# opt2bnc_trigger.net
KiCad netlist of a schematic drawn in EAGLE
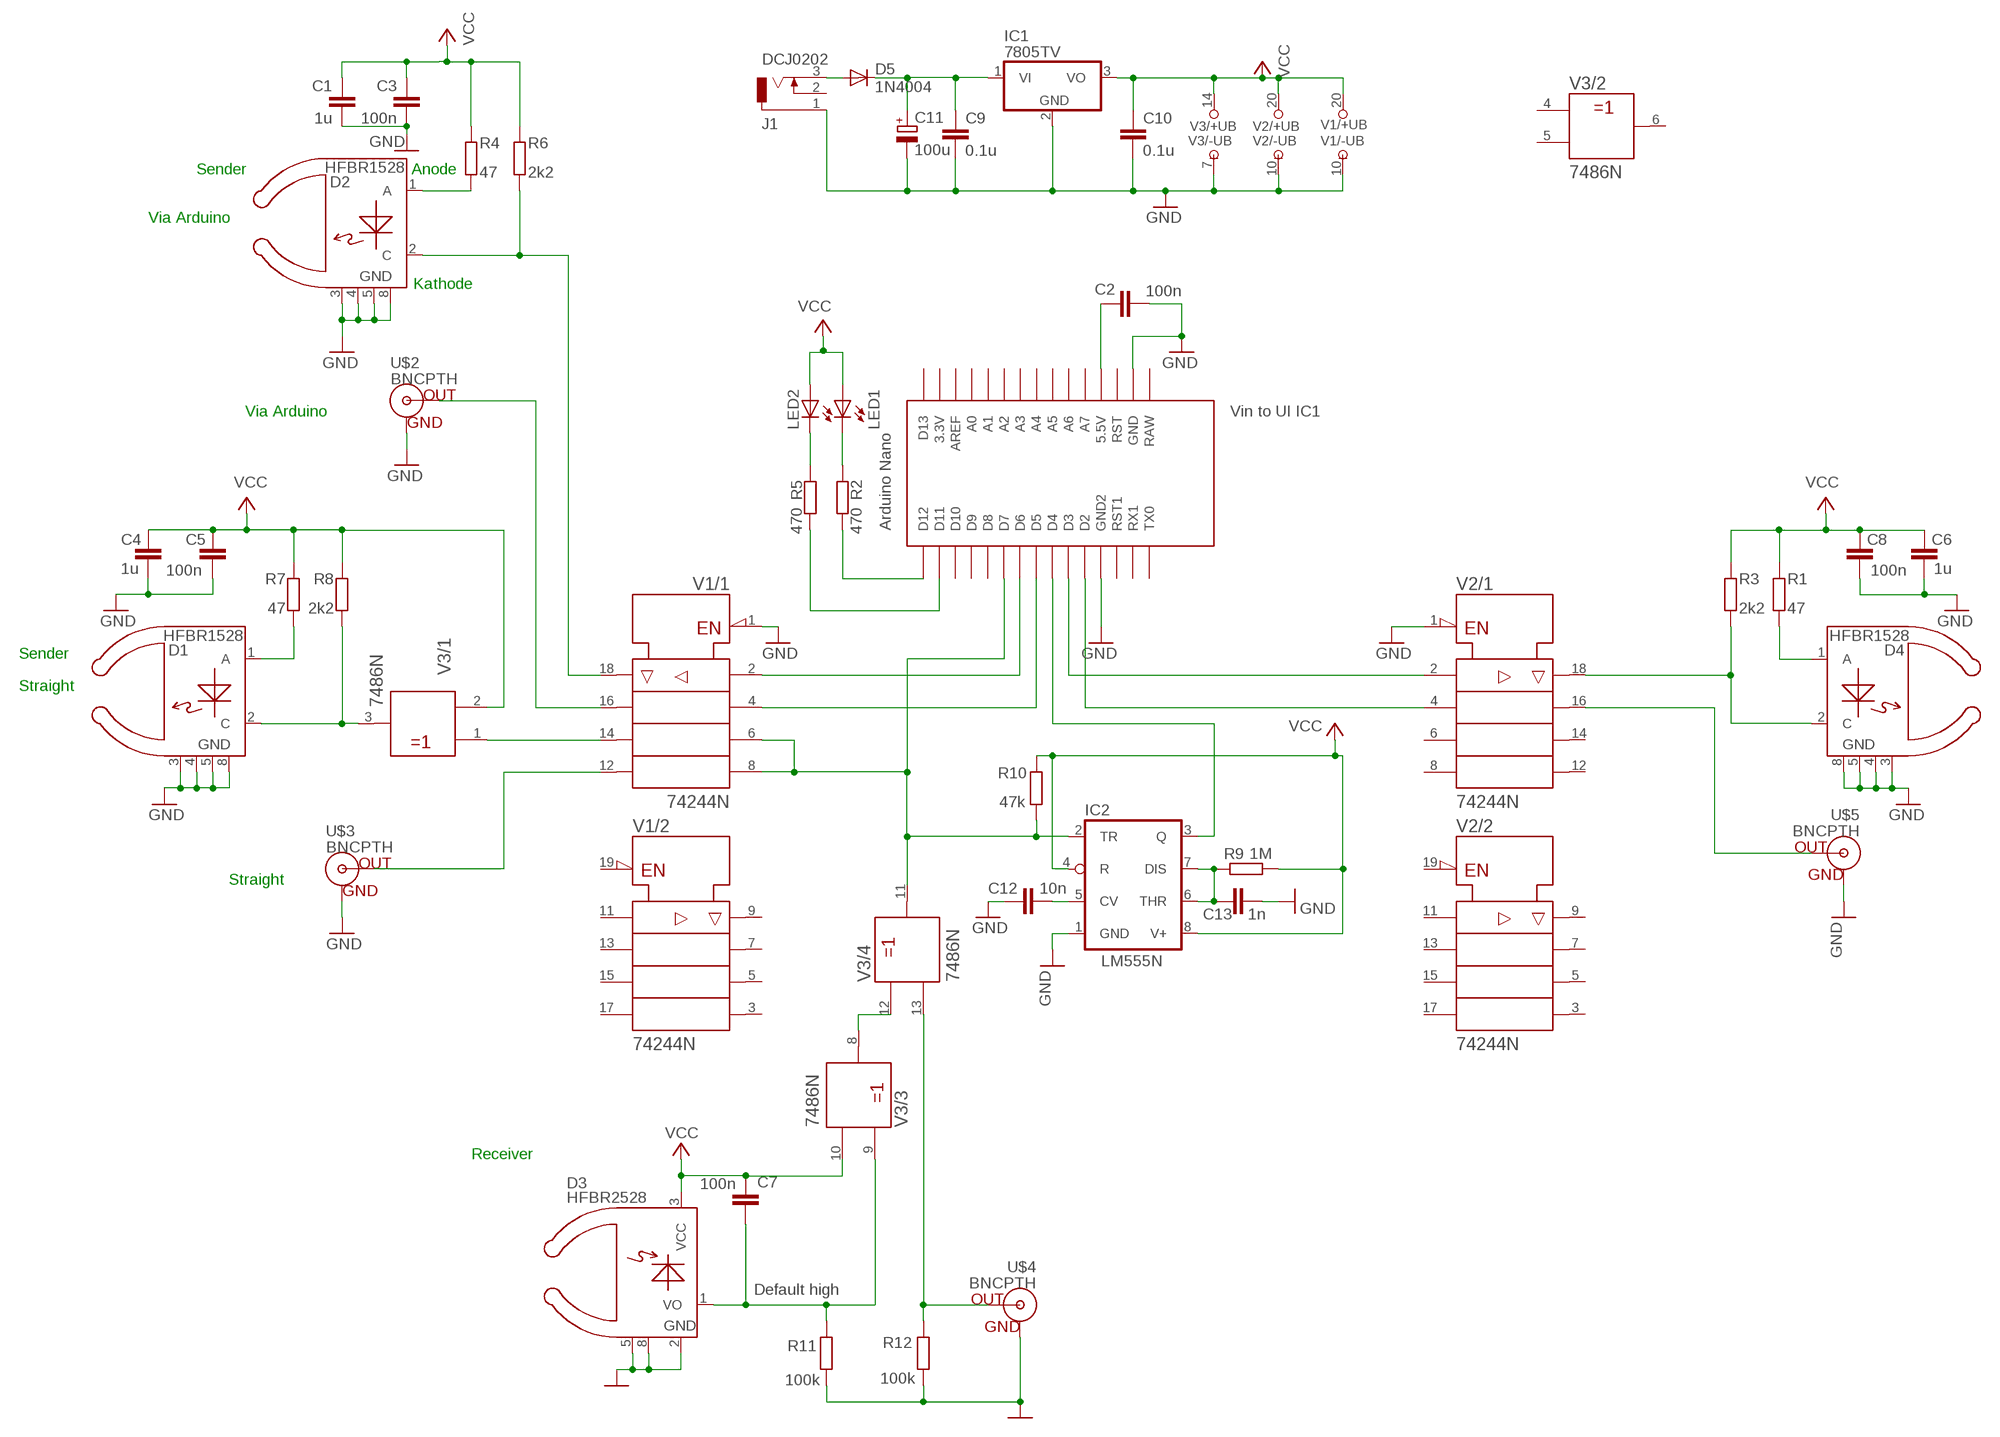
[diagram p0: schematic, sheet 1]

(export (version "E")
  (design (tool "Eeschema 10.0.6"))
  (components
    (comp (ref "C1")
      (value "1u")
      (footprint "eagle-import:C025-025X050")
      (libsource (lib "eagle-import") (part "C-EU025-025X050"))
    )
    (comp (ref "C2")
      (value "100n")
      (footprint "eagle-import:C025-025X050")
      (libsource (lib "eagle-import") (part "C-EU025-025X050"))
    )
    (comp (ref "C3")
      (value "100n")
      (footprint "eagle-import:C025-025X050")
      (libsource (lib "eagle-import") (part "C-EU025-025X050"))
    )
    (comp (ref "C4")
      (value "1u")
      (footprint "eagle-import:C025-025X050")
      (libsource (lib "eagle-import") (part "C-EU025-025X050"))
    )
    (comp (ref "C5")
      (value "100n")
      (footprint "eagle-import:C025-025X050")
      (libsource (lib "eagle-import") (part "C-EU025-025X050"))
    )
    (comp (ref "C6")
      (value "1u")
      (footprint "eagle-import:C025-025X050")
      (libsource (lib "eagle-import") (part "C-EU025-025X050"))
    )
    (comp (ref "C7")
      (value "100n")
      (footprint "eagle-import:C025-025X050")
      (libsource (lib "eagle-import") (part "C-EU025-025X050"))
    )
    (comp (ref "C8")
      (value "100n")
      (footprint "eagle-import:C025-025X050")
      (libsource (lib "eagle-import") (part "C-EU025-025X050"))
    )
    (comp (ref "C9")
      (value "0.1u")
      (footprint "eagle-import:C025-024X044")
      (libsource (lib "eagle-import") (part "C-EU025-024X044"))
    )
    (comp (ref "C10")
      (value "0.1u")
      (footprint "eagle-import:C025-024X044")
      (libsource (lib "eagle-import") (part "C-EU025-024X044"))
    )
    (comp (ref "C11")
      (value "100u")
      (footprint "eagle-import:E2-4")
      (libsource (lib "eagle-import") (part "CPOL-EUE2-4"))
    )
    (comp (ref "C12")
      (value "10n")
      (footprint "eagle-import:C025-025X050")
      (libsource (lib "eagle-import") (part "C-EU025-025X050"))
    )
    (comp (ref "C13")
      (value "1n")
      (footprint "eagle-import:C025-025X050")
      (libsource (lib "eagle-import") (part "C-EU025-025X050"))
    )
    (comp (ref "D1")
      (value "HFBR1528")
      (footprint "eagle-import:HFBR25XX")
      (fields (field (name "MF") "AGILENT TECHNOLOGIES") (field (name "MPN") "HFBR-1528"))
      (libsource (lib "eagle-import") (part "HFBR1528"))
    )
    (comp (ref "D2")
      (value "HFBR1528")
      (footprint "eagle-import:HFBR25XX")
      (fields (field (name "MF") "AGILENT TECHNOLOGIES") (field (name "MPN") "HFBR-1528"))
      (libsource (lib "eagle-import") (part "HFBR1528"))
    )
    (comp (ref "D3")
      (value "HFBR2528")
      (footprint "eagle-import:HFBR25XX")
      (fields (field (name "MF") "AGILENT TECHNOLOGIES") (field (name "MPN") "HFBR-2528"))
      (libsource (lib "eagle-import") (part "HFBR2528"))
    )
    (comp (ref "D4")
      (value "HFBR1528")
      (footprint "eagle-import:HFBR25XX")
      (fields (field (name "MF") "AGILENT TECHNOLOGIES") (field (name "MPN") "HFBR-1528"))
      (libsource (lib "eagle-import") (part "HFBR1528"))
    )
    (comp (ref "D5")
      (value "1N4004")
      (footprint "eagle-import:DO41-10")
      (libsource (lib "eagle-import") (part "1N4004"))
    )
    (comp (ref "IC1")
      (value "7805TV")
      (footprint "eagle-import:TO220V")
      (libsource (lib "eagle-import") (part "78TV05"))
    )
    (comp (ref "IC2")
      (value "LM555N")
      (footprint "eagle-import:DIL08")
      (libsource (lib "eagle-import") (part "555NLM"))
    )
    (comp (ref "J1")
      (value "DCJ0202")
      (footprint "eagle-import:DCJ0202")
      (libsource (lib "eagle-import") (part "DCJ0202"))
    )
    (comp (ref "LED1")
      (value "LED3MM")
      (footprint "eagle-import:LED3MM")
      (libsource (lib "eagle-import") (part "LED3MM"))
    )
    (comp (ref "LED2")
      (value "LED3MM")
      (footprint "eagle-import:LED3MM")
      (libsource (lib "eagle-import") (part "LED3MM"))
    )
    (comp (ref "R1")
      (value "47")
      (footprint "eagle-import:0207_7")
      (libsource (lib "eagle-import") (part "R-EU_0207/7"))
    )
    (comp (ref "R2")
      (value "470")
      (footprint "eagle-import:0207_7")
      (libsource (lib "eagle-import") (part "R-EU_0207/7"))
    )
    (comp (ref "R3")
      (value "2k2")
      (footprint "eagle-import:0207_7")
      (libsource (lib "eagle-import") (part "R-EU_0207/7"))
    )
    (comp (ref "R4")
      (value "47")
      (footprint "eagle-import:0207_7")
      (libsource (lib "eagle-import") (part "R-EU_0207/7"))
    )
    (comp (ref "R5")
      (value "470")
      (footprint "eagle-import:0207_7")
      (libsource (lib "eagle-import") (part "R-EU_0207/7"))
    )
    (comp (ref "R6")
      (value "2k2")
      (footprint "eagle-import:0207_7")
      (libsource (lib "eagle-import") (part "R-EU_0207/7"))
    )
    (comp (ref "R7")
      (value "47")
      (footprint "eagle-import:0207_7")
      (libsource (lib "eagle-import") (part "R-EU_0207/7"))
    )
    (comp (ref "R8")
      (value "2k2")
      (footprint "eagle-import:0207_7")
      (libsource (lib "eagle-import") (part "R-EU_0207/7"))
    )
    (comp (ref "R9")
      (value "1M")
      (footprint "eagle-import:0207_7")
      (libsource (lib "eagle-import") (part "R-EU_0207/7"))
    )
    (comp (ref "R10")
      (value "47k")
      (footprint "eagle-import:0207_7")
      (libsource (lib "eagle-import") (part "R-EU_0207/7"))
    )
    (comp (ref "R11")
      (value "100k")
      (footprint "eagle-import:0207_7")
      (libsource (lib "eagle-import") (part "R-EU_0207/7"))
    )
    (comp (ref "R12")
      (value "100k")
      (footprint "eagle-import:0207_7")
      (libsource (lib "eagle-import") (part "R-EU_0207/7"))
    )
    (comp (ref "U$1")
      (value "NANO")
      (footprint "eagle-import:NANO")
      (libsource (lib "eagle-import") (part "NANO"))
    )
    (comp (ref "U$2")
      (value "BNCPTH")
      (footprint "eagle-import:BNC")
      (libsource (lib "eagle-import") (part "BNCPTH"))
    )
    (comp (ref "U$3")
      (value "BNCPTH")
      (footprint "eagle-import:BNC")
      (libsource (lib "eagle-import") (part "BNCPTH"))
    )
    (comp (ref "U$4")
      (value "BNCPTH")
      (footprint "eagle-import:BNC")
      (libsource (lib "eagle-import") (part "BNCPTH"))
    )
    (comp (ref "U$5")
      (value "BNCPTH")
      (footprint "eagle-import:BNC")
      (libsource (lib "eagle-import") (part "BNCPTH"))
    )
    (comp (ref "V1")
      (value "74244N")
      (footprint "eagle-import:DIL20")
      (libsource (lib "eagle-import") (part "74244N"))
    )
    (comp (ref "V2")
      (value "74244N")
      (footprint "eagle-import:DIL20")
      (libsource (lib "eagle-import") (part "74244N"))
    )
    (comp (ref "V3")
      (value "7486N")
      (footprint "eagle-import:DIL14")
      (libsource (lib "eagle-import") (part "7486N"))
    )
  )
  (nets
    (net (code "1") (name "GND") (class "Default")
      (node (ref "C1") (pin "2") (pinfunction "2_2") (pintype "passive"))
      (node (ref "C10") (pin "2") (pinfunction "2_2") (pintype "passive"))
      (node (ref "C11") (pin "-") (pinfunction "-_-") (pintype "passive"))
      (node (ref "C12") (pin "1") (pinfunction "1_1") (pintype "passive"))
      (node (ref "C13") (pin "2") (pinfunction "2_2") (pintype "passive"))
      (node (ref "C2") (pin "2") (pinfunction "2_2") (pintype "passive"))
      (node (ref "C3") (pin "2") (pinfunction "2_2") (pintype "passive"))
      (node (ref "C4") (pin "2") (pinfunction "2_2") (pintype "passive"))
      (node (ref "C5") (pin "2") (pinfunction "2_2") (pintype "passive"))
      (node (ref "C6") (pin "2") (pinfunction "2_2") (pintype "passive"))
      (node (ref "C8") (pin "2") (pinfunction "2_2") (pintype "passive"))
      (node (ref "C9") (pin "2") (pinfunction "2_2") (pintype "passive"))
      (node (ref "D1") (pin "3") (pinfunction "1_3") (pintype "passive"))
      (node (ref "D1") (pin "4") (pinfunction "4_4") (pintype "passive"))
      (node (ref "D1") (pin "5") (pinfunction "GND_5") (pintype "passive"))
      (node (ref "D1") (pin "8") (pinfunction "GND_8") (pintype "passive"))
      (node (ref "D2") (pin "3") (pinfunction "1_3") (pintype "passive"))
      (node (ref "D2") (pin "4") (pinfunction "4_4") (pintype "passive"))
      (node (ref "D2") (pin "5") (pinfunction "GND_5") (pintype "passive"))
      (node (ref "D2") (pin "8") (pinfunction "GND_8") (pintype "passive"))
      (node (ref "D3") (pin "2") (pinfunction "GND_2") (pintype "passive"))
      (node (ref "D3") (pin "5") (pinfunction "1_5") (pintype "passive"))
      (node (ref "D3") (pin "8") (pinfunction "4_8") (pintype "passive"))
      (node (ref "D4") (pin "3") (pinfunction "1_3") (pintype "passive"))
      (node (ref "D4") (pin "4") (pinfunction "4_4") (pintype "passive"))
      (node (ref "D4") (pin "5") (pinfunction "GND_5") (pintype "passive"))
      (node (ref "D4") (pin "8") (pinfunction "GND_8") (pintype "passive"))
      (node (ref "IC1") (pin "2") (pinfunction "GND_2") (pintype "passive"))
      (node (ref "IC2") (pin "1") (pinfunction "GND_1") (pintype "power_in"))
      (node (ref "J1") (pin "1") (pinfunction "1_1") (pintype "passive"))
      (node (ref "R11") (pin "2") (pinfunction "2_2") (pintype "passive"))
      (node (ref "R12") (pin "2") (pinfunction "2_2") (pintype "passive"))
      (node (ref "U$1") (pin "GND") (pinfunction "GND_GND") (pintype "bidirectional"))
      (node (ref "U$1") (pin "GND1") (pinfunction "GND2_GND1") (pintype "bidirectional"))
      (node (ref "U$2") (pin "GND") (pinfunction "GND_GND") (pintype "bidirectional"))
      (node (ref "U$3") (pin "GND") (pinfunction "GND_GND") (pintype "bidirectional"))
      (node (ref "U$4") (pin "GND") (pinfunction "GND_GND") (pintype "bidirectional"))
      (node (ref "U$5") (pin "GND") (pinfunction "GND_GND") (pintype "bidirectional"))
      (node (ref "V1") (pin "1") (pinfunction "~{G}_1") (pintype "input"))
      (node (ref "V1") (pin "10") (pinfunction "-UB_10") (pintype "power_in"))
      (node (ref "V2") (pin "1") (pinfunction "~{G}_1") (pintype "input"))
      (node (ref "V2") (pin "10") (pinfunction "-UB_10") (pintype "power_in"))
      (node (ref "V3") (pin "7") (pinfunction "-UB_7") (pintype "power_in"))
    )
    (net (code "2") (name "Net-(D1-A)") (class "Default")
      (node (ref "D1") (pin "1") (pinfunction "A_1") (pintype "passive"))
      (node (ref "R7") (pin "1") (pinfunction "1_1") (pintype "passive"))
    )
    (net (code "3") (name "Net-(D1-C)") (class "Default")
      (node (ref "D1") (pin "2") (pinfunction "C_2") (pintype "passive"))
      (node (ref "R8") (pin "1") (pinfunction "1_1") (pintype "passive"))
      (node (ref "V3") (pin "3") (pinfunction "Y_3") (pintype "output"))
    )
    (net (code "4") (name "Net-(D2-A)") (class "Default")
      (node (ref "D2") (pin "1") (pinfunction "A_1") (pintype "passive"))
      (node (ref "R4") (pin "1") (pinfunction "1_1") (pintype "passive"))
    )
    (net (code "5") (name "Net-(D2-C)") (class "Default")
      (node (ref "D2") (pin "2") (pinfunction "C_2") (pintype "passive"))
      (node (ref "R6") (pin "1") (pinfunction "1_1") (pintype "passive"))
      (node (ref "V1") (pin "18") (pinfunction "Y1_18") (pintype "tri_state"))
    )
    (net (code "6") (name "Net-(D3-VO)") (class "Default")
      (node (ref "C7") (pin "1") (pinfunction "1_1") (pintype "passive"))
      (node (ref "D3") (pin "1") (pinfunction "VO_1") (pintype "output"))
      (node (ref "R11") (pin "1") (pinfunction "1_1") (pintype "passive"))
      (node (ref "V3") (pin "9") (pinfunction "A_9") (pintype "input"))
    )
    (net (code "7") (name "Net-(D4-A)") (class "Default")
      (node (ref "D4") (pin "1") (pinfunction "A_1") (pintype "passive"))
      (node (ref "R1") (pin "1") (pinfunction "1_1") (pintype "passive"))
    )
    (net (code "8") (name "Net-(D4-C)") (class "Default")
      (node (ref "D4") (pin "2") (pinfunction "C_2") (pintype "passive"))
      (node (ref "R3") (pin "1") (pinfunction "1_1") (pintype "passive"))
      (node (ref "V2") (pin "18") (pinfunction "Y1_18") (pintype "tri_state"))
    )
    (net (code "9") (name "Net-(D5-PadA)") (class "Default")
      (node (ref "D5") (pin "A") (pinfunction "A_A") (pintype "passive"))
      (node (ref "J1") (pin "3") (pinfunction "3_3") (pintype "passive"))
    )
    (net (code "10") (name "Net-(IC1-VI)") (class "Default")
      (node (ref "C11") (pin "+") (pinfunction "+_+") (pintype "passive"))
      (node (ref "C9") (pin "1") (pinfunction "1_1") (pintype "passive"))
      (node (ref "D5") (pin "C") (pinfunction "C_C") (pintype "passive"))
      (node (ref "IC1") (pin "1") (pinfunction "VI_1") (pintype "input"))
    )
    (net (code "11") (name "Net-(IC2-CV)") (class "Default")
      (node (ref "C12") (pin "2") (pinfunction "2_2") (pintype "passive"))
      (node (ref "IC2") (pin "5") (pinfunction "CV_5") (pintype "input"))
    )
    (net (code "12") (name "Net-(IC2-DIS)") (class "Default")
      (node (ref "C13") (pin "1") (pinfunction "1_1") (pintype "passive"))
      (node (ref "IC2") (pin "6") (pinfunction "THR_6") (pintype "input"))
      (node (ref "IC2") (pin "7") (pinfunction "DIS_7") (pintype "input"))
      (node (ref "R9") (pin "2") (pinfunction "2_2") (pintype "passive"))
    )
    (net (code "13") (name "Net-(IC2-Q)") (class "Default")
      (node (ref "IC2") (pin "3") (pinfunction "Q_3") (pintype "output"))
      (node (ref "U$1") (pin "D4") (pinfunction "D4_D4") (pintype "bidirectional"))
    )
    (net (code "14") (name "Net-(IC2-TR)") (class "Default")
      (node (ref "IC2") (pin "2") (pinfunction "TR_2") (pintype "input"))
      (node (ref "R10") (pin "2") (pinfunction "2_2") (pintype "passive"))
      (node (ref "U$1") (pin "D7") (pinfunction "D7_D7") (pintype "bidirectional"))
      (node (ref "V1") (pin "6") (pinfunction "A3_6") (pintype "input"))
      (node (ref "V1") (pin "8") (pinfunction "A4_8") (pintype "input"))
      (node (ref "V3") (pin "11") (pinfunction "Y_11") (pintype "output"))
    )
    (net (code "15") (name "Net-(LED1-C)") (class "Default")
      (node (ref "LED1") (pin "K") (pinfunction "C_K") (pintype "passive"))
      (node (ref "R2") (pin "1") (pinfunction "1_1") (pintype "passive"))
    )
    (net (code "16") (name "Net-(LED2-C)") (class "Default")
      (node (ref "LED2") (pin "K") (pinfunction "C_K") (pintype "passive"))
      (node (ref "R5") (pin "1") (pinfunction "1_1") (pintype "passive"))
    )
    (net (code "17") (name "Net-(R2-Pad2)") (class "Default")
      (node (ref "R2") (pin "2") (pinfunction "2_2") (pintype "passive"))
      (node (ref "U$1") (pin "D12") (pinfunction "D12_D12") (pintype "bidirectional"))
    )
    (net (code "18") (name "Net-(R5-Pad2)") (class "Default")
      (node (ref "R5") (pin "2") (pinfunction "2_2") (pintype "passive"))
      (node (ref "U$1") (pin "D11") (pinfunction "D11_D11") (pintype "bidirectional"))
    )
    (net (code "19") (name "Net-(U$1-5.5V)") (class "Default")
      (node (ref "C2") (pin "1") (pinfunction "1_1") (pintype "passive"))
      (node (ref "U$1") (pin "5V") (pinfunction "5.5V_5V") (pintype "bidirectional"))
    )
    (net (code "20") (name "Net-(U$2-OUT)") (class "Default")
      (node (ref "U$2") (pin "S") (pinfunction "OUT_S") (pintype "bidirectional"))
      (node (ref "V1") (pin "16") (pinfunction "Y2_16") (pintype "tri_state"))
    )
    (net (code "21") (name "Net-(U$3-OUT)") (class "Default")
      (node (ref "U$3") (pin "S") (pinfunction "OUT_S") (pintype "bidirectional"))
      (node (ref "V1") (pin "12") (pinfunction "Y4_12") (pintype "tri_state"))
    )
    (net (code "22") (name "Net-(U$4-OUT)") (class "Default")
      (node (ref "R12") (pin "1") (pinfunction "1_1") (pintype "passive"))
      (node (ref "U$4") (pin "S") (pinfunction "OUT_S") (pintype "bidirectional"))
      (node (ref "V3") (pin "13") (pinfunction "B_13") (pintype "input"))
    )
    (net (code "23") (name "Net-(U$5-OUT)") (class "Default")
      (node (ref "U$5") (pin "S") (pinfunction "OUT_S") (pintype "bidirectional"))
      (node (ref "V2") (pin "16") (pinfunction "Y2_16") (pintype "tri_state"))
    )
    (net (code "24") (name "Net-(V1C-A1)") (class "Default")
      (node (ref "U$1") (pin "D6") (pinfunction "D6_D6") (pintype "bidirectional"))
      (node (ref "V1") (pin "2") (pinfunction "A1_2") (pintype "input"))
    )
    (net (code "25") (name "Net-(V1C-A2)") (class "Default")
      (node (ref "U$1") (pin "D5") (pinfunction "D5_D5") (pintype "bidirectional"))
      (node (ref "V1") (pin "4") (pinfunction "A2_4") (pintype "input"))
    )
    (net (code "26") (name "Net-(V1C-Y3)") (class "Default")
      (node (ref "V1") (pin "14") (pinfunction "Y3_14") (pintype "tri_state"))
      (node (ref "V3") (pin "1") (pinfunction "A_1") (pintype "input"))
    )
    (net (code "27") (name "Net-(V2C-A1)") (class "Default")
      (node (ref "U$1") (pin "D3") (pinfunction "D3_D3") (pintype "bidirectional"))
      (node (ref "V2") (pin "2") (pinfunction "A1_2") (pintype "input"))
    )
    (net (code "28") (name "Net-(V2C-A2)") (class "Default")
      (node (ref "U$1") (pin "D2") (pinfunction "D2_D2") (pintype "bidirectional"))
      (node (ref "V2") (pin "4") (pinfunction "A2_4") (pintype "input"))
    )
    (net (code "29") (name "Net-(V3E-Y)") (class "Default")
      (node (ref "V3") (pin "12") (pinfunction "A_12") (pintype "input"))
      (node (ref "V3") (pin "8") (pinfunction "Y_8") (pintype "output"))
    )
    (net (code "30") (name "VCC") (class "Default")
      (node (ref "C1") (pin "1") (pinfunction "1_1") (pintype "passive"))
      (node (ref "C10") (pin "1") (pinfunction "1_1") (pintype "passive"))
      (node (ref "C3") (pin "1") (pinfunction "1_1") (pintype "passive"))
      (node (ref "C4") (pin "1") (pinfunction "1_1") (pintype "passive"))
      (node (ref "C5") (pin "1") (pinfunction "1_1") (pintype "passive"))
      (node (ref "C6") (pin "1") (pinfunction "1_1") (pintype "passive"))
      (node (ref "C7") (pin "2") (pinfunction "2_2") (pintype "passive"))
      (node (ref "C8") (pin "1") (pinfunction "1_1") (pintype "passive"))
      (node (ref "D3") (pin "3") (pinfunction "VCC_3") (pintype "passive"))
      (node (ref "IC1") (pin "3") (pinfunction "VO_3") (pintype "passive"))
      (node (ref "IC2") (pin "4") (pinfunction "R_4") (pintype "input"))
      (node (ref "IC2") (pin "8") (pinfunction "V+_8") (pintype "power_in"))
      (node (ref "LED1") (pin "A") (pinfunction "A_A") (pintype "passive"))
      (node (ref "LED2") (pin "A") (pinfunction "A_A") (pintype "passive"))
      (node (ref "R1") (pin "2") (pinfunction "2_2") (pintype "passive"))
      (node (ref "R10") (pin "1") (pinfunction "1_1") (pintype "passive"))
      (node (ref "R3") (pin "2") (pinfunction "2_2") (pintype "passive"))
      (node (ref "R4") (pin "2") (pinfunction "2_2") (pintype "passive"))
      (node (ref "R6") (pin "2") (pinfunction "2_2") (pintype "passive"))
      (node (ref "R7") (pin "2") (pinfunction "2_2") (pintype "passive"))
      (node (ref "R8") (pin "2") (pinfunction "2_2") (pintype "passive"))
      (node (ref "R9") (pin "1") (pinfunction "1_1") (pintype "passive"))
      (node (ref "V1") (pin "20") (pinfunction "+UB_20") (pintype "power_in"))
      (node (ref "V2") (pin "20") (pinfunction "+UB_20") (pintype "power_in"))
      (node (ref "V3") (pin "10") (pinfunction "B_10") (pintype "input"))
      (node (ref "V3") (pin "14") (pinfunction "+UB_14") (pintype "power_in"))
      (node (ref "V3") (pin "2") (pinfunction "B_2") (pintype "input"))
    )
    (net (code "31") (name "unconnected-(J1-Pad2)") (class "Default")
      (node (ref "J1") (pin "2") (pinfunction "2_2") (pintype "passive"))
    )
    (net (code "32") (name "unconnected-(U$1-Pad3.3V)") (class "Default")
      (node (ref "U$1") (pin "3.3V") (pinfunction "3.3V_3.3V") (pintype "bidirectional"))
    )
    (net (code "33") (name "unconnected-(U$1-PadA0)") (class "Default")
      (node (ref "U$1") (pin "A0") (pinfunction "A0_A0") (pintype "bidirectional"))
    )
    (net (code "34") (name "unconnected-(U$1-PadA1)") (class "Default")
      (node (ref "U$1") (pin "A1") (pinfunction "A1_A1") (pintype "bidirectional"))
    )
    (net (code "35") (name "unconnected-(U$1-PadA2)") (class "Default")
      (node (ref "U$1") (pin "A2") (pinfunction "A2_A2") (pintype "bidirectional"))
    )
    (net (code "36") (name "unconnected-(U$1-PadA3)") (class "Default")
      (node (ref "U$1") (pin "A3") (pinfunction "A3_A3") (pintype "bidirectional"))
    )
    (net (code "37") (name "unconnected-(U$1-PadA4)") (class "Default")
      (node (ref "U$1") (pin "A4") (pinfunction "A4_A4") (pintype "bidirectional"))
    )
    (net (code "38") (name "unconnected-(U$1-PadA5)") (class "Default")
      (node (ref "U$1") (pin "A5") (pinfunction "A5_A5") (pintype "bidirectional"))
    )
    (net (code "39") (name "unconnected-(U$1-PadA6)") (class "Default")
      (node (ref "U$1") (pin "A6") (pinfunction "A6_A6") (pintype "bidirectional"))
    )
    (net (code "40") (name "unconnected-(U$1-PadA7)") (class "Default")
      (node (ref "U$1") (pin "A7") (pinfunction "A7_A7") (pintype "bidirectional"))
    )
    (net (code "41") (name "unconnected-(U$1-PadAREF)") (class "Default")
      (node (ref "U$1") (pin "AREF") (pinfunction "AREF_AREF") (pintype "bidirectional"))
    )
    (net (code "42") (name "unconnected-(U$1-PadD8)") (class "Default")
      (node (ref "U$1") (pin "D8") (pinfunction "D8_D8") (pintype "bidirectional"))
    )
    (net (code "43") (name "unconnected-(U$1-PadD9)") (class "Default")
      (node (ref "U$1") (pin "D9") (pinfunction "D9_D9") (pintype "bidirectional"))
    )
    (net (code "44") (name "unconnected-(U$1-PadD10)") (class "Default")
      (node (ref "U$1") (pin "D10") (pinfunction "D10_D10") (pintype "bidirectional"))
    )
    (net (code "45") (name "unconnected-(U$1-PadD13)") (class "Default")
      (node (ref "U$1") (pin "D13") (pinfunction "D13_D13") (pintype "bidirectional"))
    )
    (net (code "46") (name "unconnected-(U$1-PadICSP1)") (class "Default")
      (node (ref "U$1") (pin "ICSP1") (pinfunction "ICSP1_ICSP1") (pintype "bidirectional"))
    )
    (net (code "47") (name "unconnected-(U$1-PadICSP2)") (class "Default")
      (node (ref "U$1") (pin "ICSP2") (pinfunction "ICSP2_ICSP2") (pintype "bidirectional"))
    )
    (net (code "48") (name "unconnected-(U$1-PadICSP3)") (class "Default")
      (node (ref "U$1") (pin "ICSP3") (pinfunction "ICSP3_ICSP3") (pintype "bidirectional"))
    )
    (net (code "49") (name "unconnected-(U$1-PadICSP4)") (class "Default")
      (node (ref "U$1") (pin "ICSP4") (pinfunction "ICSP4_ICSP4") (pintype "bidirectional"))
    )
    (net (code "50") (name "unconnected-(U$1-PadICSP5)") (class "Default")
      (node (ref "U$1") (pin "ICSP5") (pinfunction "ICSP5_ICSP5") (pintype "bidirectional"))
    )
    (net (code "51") (name "unconnected-(U$1-PadICSP6)") (class "Default")
      (node (ref "U$1") (pin "ICSP6") (pinfunction "ICSP6_ICSP6") (pintype "bidirectional"))
    )
    (net (code "52") (name "unconnected-(U$1-PadRAW)") (class "Default")
      (node (ref "U$1") (pin "RAW") (pinfunction "RAW_RAW") (pintype "bidirectional"))
    )
    (net (code "53") (name "unconnected-(U$1-PadRST)") (class "Default")
      (node (ref "U$1") (pin "RST") (pinfunction "RST_RST") (pintype "bidirectional"))
    )
    (net (code "54") (name "unconnected-(U$1-PadRST1)") (class "Default")
      (node (ref "U$1") (pin "RST1") (pinfunction "RST1_RST1") (pintype "bidirectional"))
    )
    (net (code "55") (name "unconnected-(U$1-PadRX1)") (class "Default")
      (node (ref "U$1") (pin "RX1") (pinfunction "RX1_RX1") (pintype "bidirectional"))
    )
    (net (code "56") (name "unconnected-(U$1-PadTX0)") (class "Default")
      (node (ref "U$1") (pin "TX0") (pinfunction "TX0_TX0") (pintype "bidirectional"))
    )
    (net (code "57") (name "unconnected-(V1D-A1-Pad11)") (class "Default")
      (node (ref "V1") (pin "11") (pinfunction "A1_11") (pintype "input"))
    )
    (net (code "58") (name "unconnected-(V1D-A2-Pad13)") (class "Default")
      (node (ref "V1") (pin "13") (pinfunction "A2_13") (pintype "input"))
    )
    (net (code "59") (name "unconnected-(V1D-A3-Pad15)") (class "Default")
      (node (ref "V1") (pin "15") (pinfunction "A3_15") (pintype "input"))
    )
    (net (code "60") (name "unconnected-(V1D-A4-Pad17)") (class "Default")
      (node (ref "V1") (pin "17") (pinfunction "A4_17") (pintype "input"))
    )
    (net (code "61") (name "unconnected-(V1D-Y1-Pad9)") (class "Default")
      (node (ref "V1") (pin "9") (pinfunction "Y1_9") (pintype "tri_state"))
    )
    (net (code "62") (name "unconnected-(V1D-Y2-Pad7)") (class "Default")
      (node (ref "V1") (pin "7") (pinfunction "Y2_7") (pintype "tri_state"))
    )
    (net (code "63") (name "unconnected-(V1D-Y3-Pad5)") (class "Default")
      (node (ref "V1") (pin "5") (pinfunction "Y3_5") (pintype "tri_state"))
    )
    (net (code "64") (name "unconnected-(V1D-Y4-Pad3)") (class "Default")
      (node (ref "V1") (pin "3") (pinfunction "Y4_3") (pintype "tri_state"))
    )
    (net (code "65") (name "unconnected-(V1D-~{G}-Pad19)") (class "Default")
      (node (ref "V1") (pin "19") (pinfunction "~{G}_19") (pintype "input"))
    )
    (net (code "66") (name "unconnected-(V2C-A3-Pad6)") (class "Default")
      (node (ref "V2") (pin "6") (pinfunction "A3_6") (pintype "input"))
    )
    (net (code "67") (name "unconnected-(V2C-A4-Pad8)") (class "Default")
      (node (ref "V2") (pin "8") (pinfunction "A4_8") (pintype "input"))
    )
    (net (code "68") (name "unconnected-(V2C-Y3-Pad14)") (class "Default")
      (node (ref "V2") (pin "14") (pinfunction "Y3_14") (pintype "tri_state"))
    )
    (net (code "69") (name "unconnected-(V2C-Y4-Pad12)") (class "Default")
      (node (ref "V2") (pin "12") (pinfunction "Y4_12") (pintype "tri_state"))
    )
    (net (code "70") (name "unconnected-(V2D-A1-Pad11)") (class "Default")
      (node (ref "V2") (pin "11") (pinfunction "A1_11") (pintype "input"))
    )
    (net (code "71") (name "unconnected-(V2D-A2-Pad13)") (class "Default")
      (node (ref "V2") (pin "13") (pinfunction "A2_13") (pintype "input"))
    )
    (net (code "72") (name "unconnected-(V2D-A3-Pad15)") (class "Default")
      (node (ref "V2") (pin "15") (pinfunction "A3_15") (pintype "input"))
    )
    (net (code "73") (name "unconnected-(V2D-A4-Pad17)") (class "Default")
      (node (ref "V2") (pin "17") (pinfunction "A4_17") (pintype "input"))
    )
    (net (code "74") (name "unconnected-(V2D-Y1-Pad9)") (class "Default")
      (node (ref "V2") (pin "9") (pinfunction "Y1_9") (pintype "tri_state"))
    )
    (net (code "75") (name "unconnected-(V2D-Y2-Pad7)") (class "Default")
      (node (ref "V2") (pin "7") (pinfunction "Y2_7") (pintype "tri_state"))
    )
    (net (code "76") (name "unconnected-(V2D-Y3-Pad5)") (class "Default")
      (node (ref "V2") (pin "5") (pinfunction "Y3_5") (pintype "tri_state"))
    )
    (net (code "77") (name "unconnected-(V2D-Y4-Pad3)") (class "Default")
      (node (ref "V2") (pin "3") (pinfunction "Y4_3") (pintype "tri_state"))
    )
    (net (code "78") (name "unconnected-(V2D-~{G}-Pad19)") (class "Default")
      (node (ref "V2") (pin "19") (pinfunction "~{G}_19") (pintype "input"))
    )
    (net (code "79") (name "unconnected-(V3D-A-Pad4)") (class "Default")
      (node (ref "V3") (pin "4") (pinfunction "A_4") (pintype "input"))
    )
    (net (code "80") (name "unconnected-(V3D-B-Pad5)") (class "Default")
      (node (ref "V3") (pin "5") (pinfunction "B_5") (pintype "input"))
    )
    (net (code "81") (name "unconnected-(V3D-Y-Pad6)") (class "Default")
      (node (ref "V3") (pin "6") (pinfunction "Y_6") (pintype "output"))
    )
  )
)
